# VCA-v2.net
KiCad netlist of a schematic drawn in EAGLE
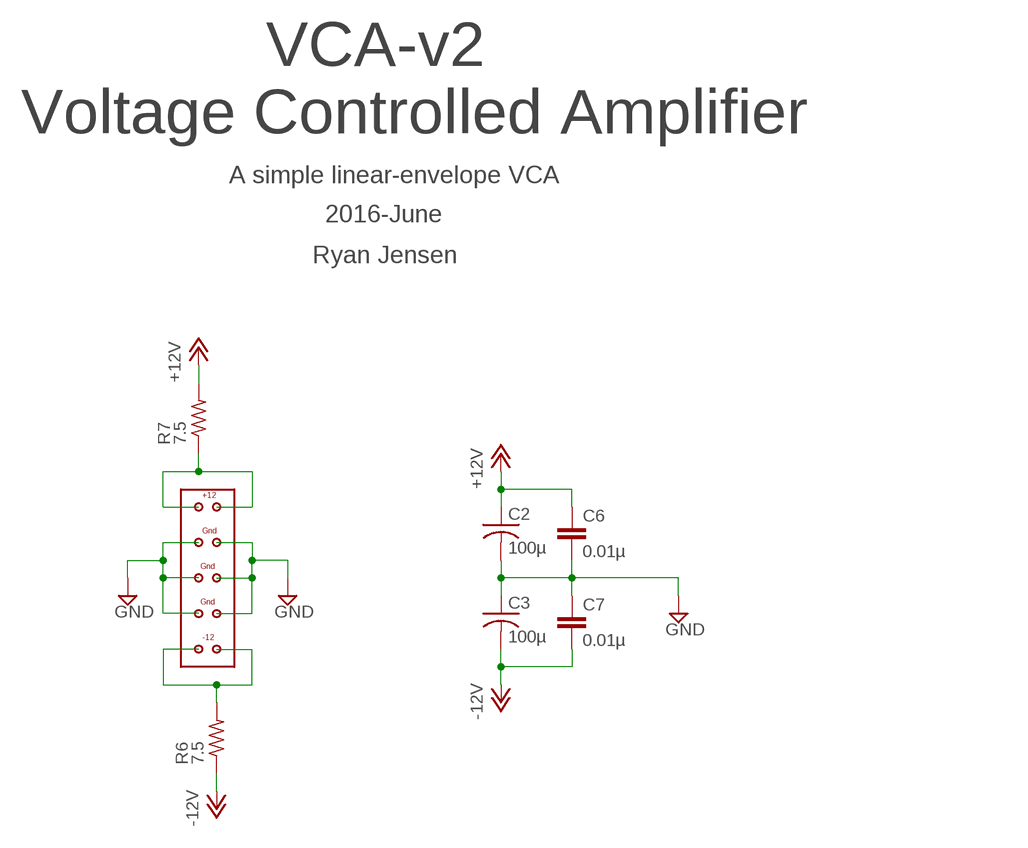
[diagram p0: schematic, sheet 1]
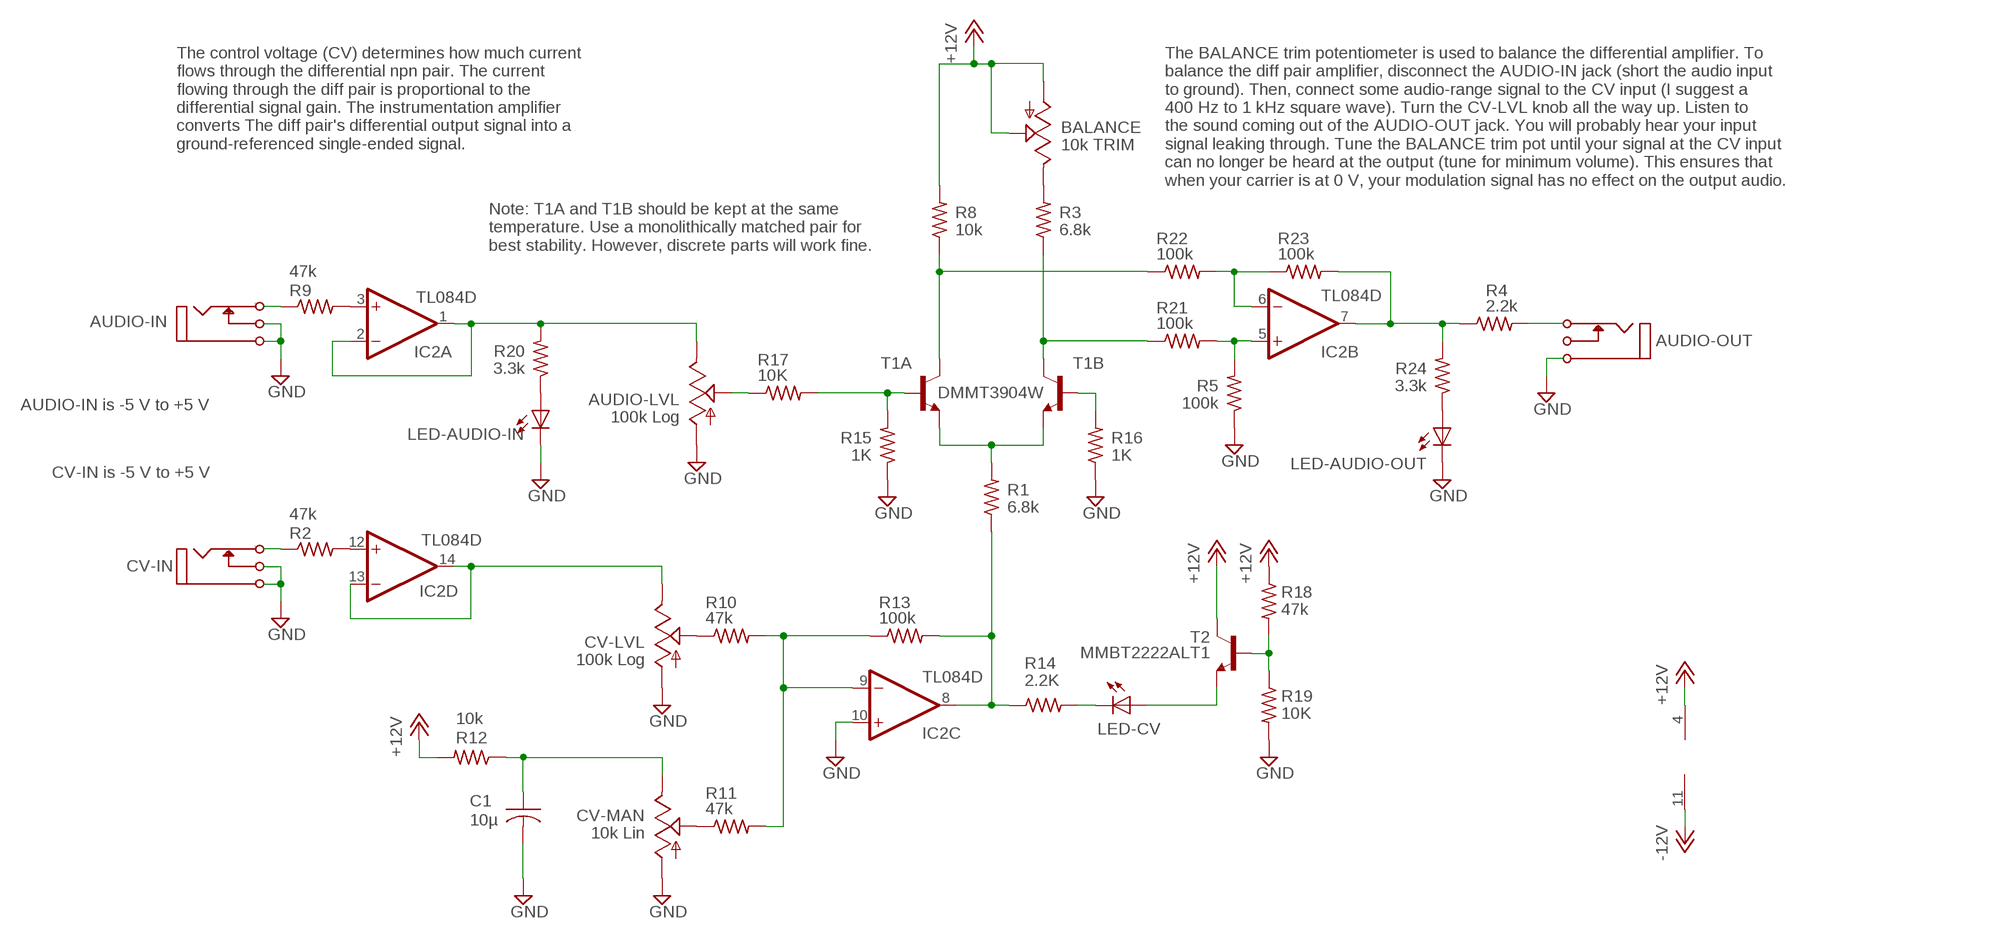
[diagram p1: schematic, sheet 2]

(export (version "E")
  (design (tool "Eeschema 10.0.6"))
  (components
    (comp (ref "C2")
      (value "100µ")
      (footprint "eagle-import:C025-050X050")
      (libsource (lib "eagle-import") (part "C-US025-050X050"))
    )
    (comp (ref "C3")
      (value "100µ")
      (footprint "eagle-import:C025-050X050")
      (libsource (lib "eagle-import") (part "C-US025-050X050"))
    )
    (comp (ref "C6")
      (value "0.01µ")
      (footprint "eagle-import:C2.5-2")
      (libsource (lib "eagle-import") (part "C2.5/2"))
    )
    (comp (ref "C7")
      (value "0.01µ")
      (footprint "eagle-import:C2.5-2")
      (libsource (lib "eagle-import") (part "C2.5/2"))
    )
    (comp (ref "R6")
      (value "7.5")
      (footprint "eagle-import:R0603")
      (libsource (lib "eagle-import") (part "R-US_R0603"))
    )
    (comp (ref "R7")
      (value "7.5")
      (footprint "eagle-import:R0603")
      (libsource (lib "eagle-import") (part "R-US_R0603"))
    )
    (comp (ref "U$1")
      (value "EURORACK-POWER")
      (footprint "eagle-import:EURORACK-POWER")
      (libsource (lib "eagle-import") (part "EURORACK-POWER"))
    )
    (comp (ref "AUDIO-IN")
      (value "I/O")
      (footprint "eagle-import:MONO_JACK")
      (libsource (lib "eagle-import") (part "MONO_JACK"))
    )
    (comp (ref "AUDIO-LVL")
      (value "100k Log")
      (footprint "eagle-import:B64Y")
      (libsource (lib "eagle-import") (part "TRIM_US-B64Y"))
    )
    (comp (ref "AUDIO-OUT")
      (value "I/O")
      (footprint "eagle-import:MONO_JACK")
      (libsource (lib "eagle-import") (part "MONO_JACK"))
    )
    (comp (ref "BALANCE")
      (value "10k TRIM")
      (footprint "eagle-import:B64Y")
      (libsource (lib "eagle-import") (part "TRIM_US-B64Y"))
    )
    (comp (ref "C1")
      (value "10µ")
      (footprint "eagle-import:C025-050X050")
      (libsource (lib "eagle-import") (part "C-US025-050X050"))
    )
    (comp (ref "CV-IN")
      (value "I/O")
      (footprint "eagle-import:MONO_JACK")
      (libsource (lib "eagle-import") (part "MONO_JACK"))
    )
    (comp (ref "CV-LVL")
      (value "100k Log")
      (footprint "eagle-import:B64Y")
      (libsource (lib "eagle-import") (part "TRIM_US-B64Y"))
    )
    (comp (ref "CV-MAN")
      (value "10k Lin")
      (footprint "eagle-import:B64Y")
      (libsource (lib "eagle-import") (part "TRIM_US-B64Y"))
    )
    (comp (ref "IC2")
      (value "TL084D")
      (footprint "eagle-import:SO14")
      (libsource (lib "eagle-import") (part "TL084D"))
    )
    (comp (ref "LED-AUDIO-IN")
      (value "TLLG4400")
      (footprint "eagle-import:LED3MM")
      (fields (field (name "MF") "VISHAY SEMICONDUCTOR"))
      (libsource (lib "eagle-import") (part "TLLG4400"))
    )
    (comp (ref "LED-AUDIO-OUT")
      (value "TLLG4400")
      (footprint "eagle-import:LED3MM")
      (fields (field (name "MF") "VISHAY SEMICONDUCTOR"))
      (libsource (lib "eagle-import") (part "TLLG4400"))
    )
    (comp (ref "LED-CV")
      (value "TLLG4400")
      (footprint "eagle-import:LED3MM")
      (fields (field (name "MF") "VISHAY SEMICONDUCTOR"))
      (libsource (lib "eagle-import") (part "TLLG4400"))
    )
    (comp (ref "R1")
      (value "6.8k")
      (footprint "eagle-import:R0603")
      (libsource (lib "eagle-import") (part "R-US_R0603"))
    )
    (comp (ref "R2")
      (value "47k")
      (footprint "eagle-import:R0603")
      (libsource (lib "eagle-import") (part "R-US_R0603"))
    )
    (comp (ref "R3")
      (value "6.8k")
      (footprint "eagle-import:R0603")
      (libsource (lib "eagle-import") (part "R-US_R0603"))
    )
    (comp (ref "R4")
      (value "2.2k")
      (footprint "eagle-import:R0603")
      (libsource (lib "eagle-import") (part "R-US_R0603"))
    )
    (comp (ref "R5")
      (value "100k")
      (footprint "eagle-import:R0603")
      (libsource (lib "eagle-import") (part "R-US_R0603"))
    )
    (comp (ref "R8")
      (value "10k")
      (footprint "eagle-import:R0603")
      (libsource (lib "eagle-import") (part "R-US_R0603"))
    )
    (comp (ref "R9")
      (value "47k")
      (footprint "eagle-import:R0603")
      (libsource (lib "eagle-import") (part "R-US_R0603"))
    )
    (comp (ref "R10")
      (value "47k")
      (footprint "eagle-import:R0603")
      (libsource (lib "eagle-import") (part "R-US_R0603"))
    )
    (comp (ref "R11")
      (value "47k")
      (footprint "eagle-import:R0603")
      (libsource (lib "eagle-import") (part "R-US_R0603"))
    )
    (comp (ref "R12")
      (value "10k")
      (footprint "eagle-import:R0603")
      (libsource (lib "eagle-import") (part "R-US_R0603"))
    )
    (comp (ref "R13")
      (value "100k")
      (footprint "eagle-import:R0603")
      (libsource (lib "eagle-import") (part "R-US_R0603"))
    )
    (comp (ref "R14")
      (value "2.2K")
      (footprint "eagle-import:R0603")
      (libsource (lib "eagle-import") (part "R-US_R0603"))
    )
    (comp (ref "R15")
      (value "1K")
      (footprint "eagle-import:R0603")
      (libsource (lib "eagle-import") (part "R-US_R0603"))
    )
    (comp (ref "R16")
      (value "1K")
      (footprint "eagle-import:R0603")
      (libsource (lib "eagle-import") (part "R-US_R0603"))
    )
    (comp (ref "R17")
      (value "10K")
      (footprint "eagle-import:R0603")
      (libsource (lib "eagle-import") (part "R-US_R0603"))
    )
    (comp (ref "R18")
      (value "47k")
      (footprint "eagle-import:R0603")
      (libsource (lib "eagle-import") (part "R-US_R0603"))
    )
    (comp (ref "R19")
      (value "10K")
      (footprint "eagle-import:R0603")
      (libsource (lib "eagle-import") (part "R-US_R0603"))
    )
    (comp (ref "R20")
      (value "3.3k")
      (footprint "eagle-import:R0603")
      (libsource (lib "eagle-import") (part "R-US_R0603"))
    )
    (comp (ref "R21")
      (value "100k")
      (footprint "eagle-import:R0603")
      (libsource (lib "eagle-import") (part "R-US_R0603"))
    )
    (comp (ref "R22")
      (value "100k")
      (footprint "eagle-import:R0603")
      (libsource (lib "eagle-import") (part "R-US_R0603"))
    )
    (comp (ref "R23")
      (value "100k")
      (footprint "eagle-import:R0603")
      (libsource (lib "eagle-import") (part "R-US_R0603"))
    )
    (comp (ref "R24")
      (value "3.3k")
      (footprint "eagle-import:R0603")
      (libsource (lib "eagle-import") (part "R-US_R0603"))
    )
    (comp (ref "T1")
      (value "DMMT3904W")
      (footprint "eagle-import:SOT363")
      (libsource (lib "eagle-import") (part "DMMT3904W"))
    )
    (comp (ref "T2")
      (value "MMBT2222ALT1")
      (footprint "eagle-import:SOT23-BEC")
      (libsource (lib "eagle-import") (part "-NPN-SOT23-BECMMBT2222ALT1"))
    )
  )
  (nets
    (net (code "1") (name "+12V") (class "Default")
      (node (ref "BALANCE") (pin "A") (pinfunction "A_A") (pintype "passive"))
      (node (ref "BALANCE") (pin "S") (pinfunction "S_S") (pintype "passive"))
      (node (ref "C2") (pin "1") (pinfunction "1_1") (pintype "passive"))
      (node (ref "C6") (pin "1") (pinfunction "1_1") (pintype "passive"))
      (node (ref "IC2") (pin "4") (pinfunction "V+_4") (pintype "power_in"))
      (node (ref "R12") (pin "2") (pinfunction "2_2") (pintype "passive"))
      (node (ref "R18") (pin "1") (pinfunction "1_1") (pintype "passive"))
      (node (ref "R7") (pin "2") (pinfunction "2_2") (pintype "passive"))
      (node (ref "R8") (pin "2") (pinfunction "2_2") (pintype "passive"))
      (node (ref "T2") (pin "C") (pinfunction "C_C") (pintype "passive"))
    )
    (net (code "2") (name "-12V") (class "Default")
      (node (ref "C3") (pin "2") (pinfunction "2_2") (pintype "passive"))
      (node (ref "C7") (pin "2") (pinfunction "2_2") (pintype "passive"))
      (node (ref "IC2") (pin "11") (pinfunction "V-_11") (pintype "power_in"))
      (node (ref "R6") (pin "1") (pinfunction "1_1") (pintype "passive"))
    )
    (net (code "3") (name "GND") (class "Default")
      (node (ref "AUDIO-IN") (pin "P$1") (pinfunction "P$1_P$1") (pintype "bidirectional"))
      (node (ref "AUDIO-IN") (pin "P$3") (pinfunction "P3_P$3") (pintype "bidirectional"))
      (node (ref "AUDIO-LVL") (pin "A") (pinfunction "A_A") (pintype "passive"))
      (node (ref "AUDIO-OUT") (pin "P$1") (pinfunction "P$1_P$1") (pintype "bidirectional"))
      (node (ref "C1") (pin "2") (pinfunction "2_2") (pintype "passive"))
      (node (ref "C2") (pin "2") (pinfunction "2_2") (pintype "passive"))
      (node (ref "C3") (pin "1") (pinfunction "1_1") (pintype "passive"))
      (node (ref "C6") (pin "2") (pinfunction "2_2") (pintype "passive"))
      (node (ref "C7") (pin "1") (pinfunction "1_1") (pintype "passive"))
      (node (ref "CV-IN") (pin "P$1") (pinfunction "P$1_P$1") (pintype "bidirectional"))
      (node (ref "CV-IN") (pin "P$3") (pinfunction "P3_P$3") (pintype "bidirectional"))
      (node (ref "CV-LVL") (pin "A") (pinfunction "A_A") (pintype "passive"))
      (node (ref "CV-MAN") (pin "A") (pinfunction "A_A") (pintype "passive"))
      (node (ref "IC2") (pin "10") (pinfunction "+IN_10") (pintype "input"))
      (node (ref "LED-AUDIO-IN") (pin "K") (pinfunction "C_K") (pintype "passive"))
      (node (ref "LED-AUDIO-OUT") (pin "K") (pinfunction "C_K") (pintype "passive"))
      (node (ref "R15") (pin "1") (pinfunction "1_1") (pintype "passive"))
      (node (ref "R16") (pin "1") (pinfunction "1_1") (pintype "passive"))
      (node (ref "R19") (pin "2") (pinfunction "2_2") (pintype "passive"))
      (node (ref "R5") (pin "1") (pinfunction "1_1") (pintype "passive"))
      (node (ref "U$1") (pin "P$3") (pinfunction "P$3_P$3") (pintype "bidirectional"))
      (node (ref "U$1") (pin "P$4") (pinfunction "P$4_P$4") (pintype "bidirectional"))
      (node (ref "U$1") (pin "P$5") (pinfunction "P$5_P$5") (pintype "bidirectional"))
      (node (ref "U$1") (pin "P$6") (pinfunction "P$6_P$6") (pintype "bidirectional"))
      (node (ref "U$1") (pin "P$7") (pinfunction "P$7_P$7") (pintype "bidirectional"))
      (node (ref "U$1") (pin "P$8") (pinfunction "P$8_P$8") (pintype "bidirectional"))
    )
    (net (code "4") (name "Net-(AUDIO-IN-P2)") (class "Default")
      (node (ref "AUDIO-IN") (pin "P$2") (pinfunction "P2_P$2") (pintype "bidirectional"))
      (node (ref "R9") (pin "1") (pinfunction "1_1") (pintype "passive"))
    )
    (net (code "5") (name "Net-(AUDIO-LVL-PadS)") (class "Default")
      (node (ref "AUDIO-LVL") (pin "S") (pinfunction "S_S") (pintype "passive"))
      (node (ref "R17") (pin "1") (pinfunction "1_1") (pintype "passive"))
    )
    (net (code "6") (name "Net-(AUDIO-OUT-P2)") (class "Default")
      (node (ref "AUDIO-OUT") (pin "P$2") (pinfunction "P2_P$2") (pintype "bidirectional"))
      (node (ref "R4") (pin "2") (pinfunction "2_2") (pintype "passive"))
    )
    (net (code "7") (name "Net-(BALANCE-PadE)") (class "Default")
      (node (ref "BALANCE") (pin "E") (pinfunction "E_E") (pintype "passive"))
      (node (ref "R3") (pin "2") (pinfunction "2_2") (pintype "passive"))
    )
    (net (code "8") (name "Net-(C1-Pad1)") (class "Default")
      (node (ref "C1") (pin "1") (pinfunction "1_1") (pintype "passive"))
      (node (ref "CV-MAN") (pin "E") (pinfunction "E_E") (pintype "passive"))
      (node (ref "R12") (pin "1") (pinfunction "1_1") (pintype "passive"))
    )
    (net (code "9") (name "Net-(CV-IN-P2)") (class "Default")
      (node (ref "CV-IN") (pin "P$2") (pinfunction "P2_P$2") (pintype "bidirectional"))
      (node (ref "R2") (pin "1") (pinfunction "1_1") (pintype "passive"))
    )
    (net (code "10") (name "Net-(CV-LVL-PadS)") (class "Default")
      (node (ref "CV-LVL") (pin "S") (pinfunction "S_S") (pintype "passive"))
      (node (ref "R10") (pin "1") (pinfunction "1_1") (pintype "passive"))
    )
    (net (code "11") (name "Net-(CV-MAN-PadS)") (class "Default")
      (node (ref "CV-MAN") (pin "S") (pinfunction "S_S") (pintype "passive"))
      (node (ref "R11") (pin "1") (pinfunction "1_1") (pintype "passive"))
    )
    (net (code "12") (name "Net-(IC2A-+IN)") (class "Default")
      (node (ref "IC2") (pin "3") (pinfunction "+IN_3") (pintype "input"))
      (node (ref "R9") (pin "2") (pinfunction "2_2") (pintype "passive"))
    )
    (net (code "13") (name "Net-(IC2A--IN)") (class "Default")
      (node (ref "AUDIO-LVL") (pin "E") (pinfunction "E_E") (pintype "passive"))
      (node (ref "IC2") (pin "1") (pinfunction "OUT_1") (pintype "output"))
      (node (ref "IC2") (pin "2") (pinfunction "-IN_2") (pintype "input"))
      (node (ref "R20") (pin "2") (pinfunction "2_2") (pintype "passive"))
    )
    (net (code "14") (name "Net-(IC2B-+IN)") (class "Default")
      (node (ref "IC2") (pin "5") (pinfunction "+IN_5") (pintype "input"))
      (node (ref "R21") (pin "2") (pinfunction "2_2") (pintype "passive"))
      (node (ref "R5") (pin "2") (pinfunction "2_2") (pintype "passive"))
    )
    (net (code "15") (name "Net-(IC2B--IN)") (class "Default")
      (node (ref "IC2") (pin "6") (pinfunction "-IN_6") (pintype "input"))
      (node (ref "R22") (pin "2") (pinfunction "2_2") (pintype "passive"))
      (node (ref "R23") (pin "1") (pinfunction "1_1") (pintype "passive"))
    )
    (net (code "16") (name "Net-(IC2B-OUT)") (class "Default")
      (node (ref "IC2") (pin "7") (pinfunction "OUT_7") (pintype "output"))
      (node (ref "R23") (pin "2") (pinfunction "2_2") (pintype "passive"))
      (node (ref "R24") (pin "2") (pinfunction "2_2") (pintype "passive"))
      (node (ref "R4") (pin "1") (pinfunction "1_1") (pintype "passive"))
    )
    (net (code "17") (name "Net-(IC2C--IN)") (class "Default")
      (node (ref "IC2") (pin "9") (pinfunction "-IN_9") (pintype "input"))
      (node (ref "R10") (pin "2") (pinfunction "2_2") (pintype "passive"))
      (node (ref "R11") (pin "2") (pinfunction "2_2") (pintype "passive"))
      (node (ref "R13") (pin "1") (pinfunction "1_1") (pintype "passive"))
    )
    (net (code "18") (name "Net-(IC2C-OUT)") (class "Default")
      (node (ref "IC2") (pin "8") (pinfunction "OUT_8") (pintype "output"))
      (node (ref "R1") (pin "1") (pinfunction "1_1") (pintype "passive"))
      (node (ref "R13") (pin "2") (pinfunction "2_2") (pintype "passive"))
      (node (ref "R14") (pin "1") (pinfunction "1_1") (pintype "passive"))
    )
    (net (code "19") (name "Net-(IC2D-+IN)") (class "Default")
      (node (ref "IC2") (pin "12") (pinfunction "+IN_12") (pintype "input"))
      (node (ref "R2") (pin "2") (pinfunction "2_2") (pintype "passive"))
    )
    (net (code "20") (name "Net-(IC2D--IN)") (class "Default")
      (node (ref "CV-LVL") (pin "E") (pinfunction "E_E") (pintype "passive"))
      (node (ref "IC2") (pin "13") (pinfunction "-IN_13") (pintype "input"))
      (node (ref "IC2") (pin "14") (pinfunction "OUT_14") (pintype "output"))
    )
    (net (code "21") (name "Net-(LED-AUDIO-IN-PadA)") (class "Default")
      (node (ref "LED-AUDIO-IN") (pin "A") (pinfunction "A_A") (pintype "passive"))
      (node (ref "R20") (pin "1") (pinfunction "1_1") (pintype "passive"))
    )
    (net (code "22") (name "Net-(LED-AUDIO-OUT-PadA)") (class "Default")
      (node (ref "LED-AUDIO-OUT") (pin "A") (pinfunction "A_A") (pintype "passive"))
      (node (ref "R24") (pin "1") (pinfunction "1_1") (pintype "passive"))
    )
    (net (code "23") (name "Net-(LED-CV-C)") (class "Default")
      (node (ref "LED-CV") (pin "K") (pinfunction "C_K") (pintype "passive"))
      (node (ref "R14") (pin "2") (pinfunction "2_2") (pintype "passive"))
    )
    (net (code "24") (name "Net-(LED-CV-PadA)") (class "Default")
      (node (ref "LED-CV") (pin "A") (pinfunction "A_A") (pintype "passive"))
      (node (ref "T2") (pin "E") (pinfunction "E_E") (pintype "passive"))
    )
    (net (code "25") (name "Net-(R6-Pad2)") (class "Default")
      (node (ref "R6") (pin "2") (pinfunction "2_2") (pintype "passive"))
      (node (ref "U$1") (pin "P$10") (pinfunction "P$10_P$10") (pintype "bidirectional"))
      (node (ref "U$1") (pin "P$9") (pinfunction "P$9_P$9") (pintype "bidirectional"))
    )
    (net (code "26") (name "Net-(R7-Pad1)") (class "Default")
      (node (ref "R7") (pin "1") (pinfunction "1_1") (pintype "passive"))
      (node (ref "U$1") (pin "P$1") (pinfunction "P$1_P$1") (pintype "bidirectional"))
      (node (ref "U$1") (pin "P$2") (pinfunction "P$2_P$2") (pintype "bidirectional"))
    )
    (net (code "27") (name "Net-(R18-Pad2)") (class "Default")
      (node (ref "R18") (pin "2") (pinfunction "2_2") (pintype "passive"))
      (node (ref "R19") (pin "1") (pinfunction "1_1") (pintype "passive"))
      (node (ref "T2") (pin "B") (pinfunction "B_B") (pintype "passive"))
    )
    (net (code "28") (name "Net-(T1A-B)") (class "Default")
      (node (ref "R15") (pin "2") (pinfunction "2_2") (pintype "passive"))
      (node (ref "R17") (pin "2") (pinfunction "2_2") (pintype "passive"))
      (node (ref "T1") (pin "1") (pinfunction "B_1") (pintype "passive"))
    )
    (net (code "29") (name "Net-(T1A-C)") (class "Default")
      (node (ref "R22") (pin "1") (pinfunction "1_1") (pintype "passive"))
      (node (ref "R8") (pin "1") (pinfunction "1_1") (pintype "passive"))
      (node (ref "T1") (pin "6") (pinfunction "C_6") (pintype "passive"))
    )
    (net (code "30") (name "Net-(T1A-E)") (class "Default")
      (node (ref "R1") (pin "2") (pinfunction "2_2") (pintype "passive"))
      (node (ref "T1") (pin "4") (pinfunction "E_4") (pintype "passive"))
      (node (ref "T1") (pin "5") (pinfunction "E_5") (pintype "passive"))
    )
    (net (code "31") (name "Net-(T1B-B)") (class "Default")
      (node (ref "R16") (pin "2") (pinfunction "2_2") (pintype "passive"))
      (node (ref "T1") (pin "2") (pinfunction "B_2") (pintype "passive"))
    )
    (net (code "32") (name "Net-(T1B-C)") (class "Default")
      (node (ref "R21") (pin "1") (pinfunction "1_1") (pintype "passive"))
      (node (ref "R3") (pin "1") (pinfunction "1_1") (pintype "passive"))
      (node (ref "T1") (pin "3") (pinfunction "C_3") (pintype "passive"))
    )
    (net (code "33") (name "unconnected-(AUDIO-OUT-P3-PadP$3)") (class "Default")
      (node (ref "AUDIO-OUT") (pin "P$3") (pinfunction "P3_P$3") (pintype "bidirectional"))
    )
  )
)
